# ADS1299.net
KiCad netlist of a schematic drawn in Altium Designer
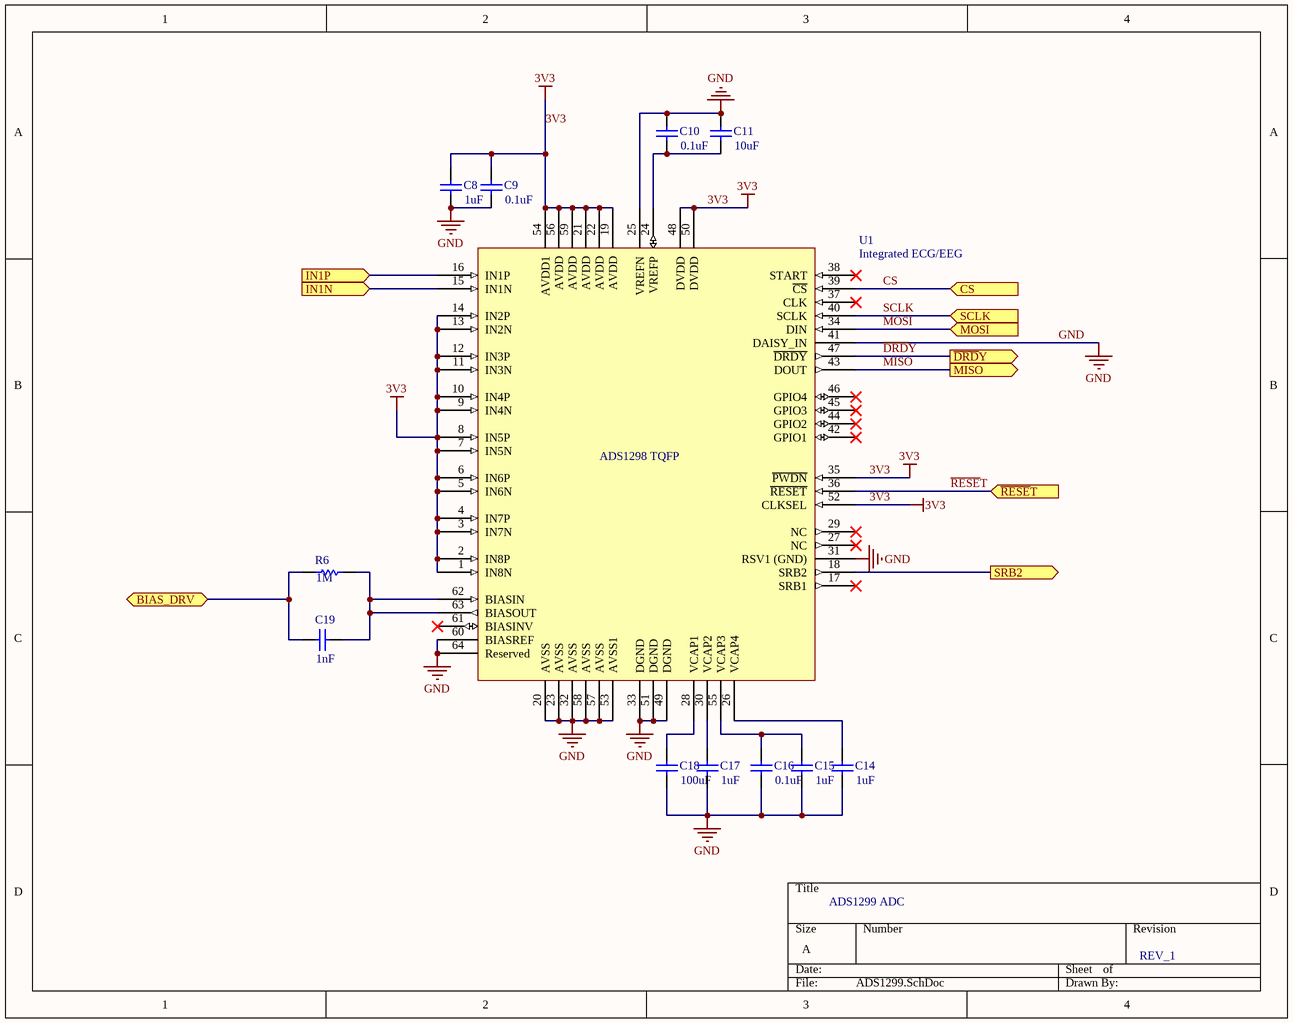
[diagram p0: ADS1299.SchDoc]

(export (version "E")
  (design (tool "Eeschema 10.0.6"))
  (components
    (comp (ref "C8")
      (value "1uF")
      (footprint "1608[0603]")
      (description "Capacitor")
      (fields (field (name "Comment") "Cap") (field (name "PUBLISHER") "Altium Limited"))
      (libsource (lib "Miscellaneous Devices") (part "Cap"))
    )
    (comp (ref "C9")
      (value "0.1uF")
      (footprint "1608[0603]")
      (description "Capacitor")
      (fields (field (name "Comment") "Cap") (field (name "PUBLISHER") "Altium Limited"))
      (libsource (lib "Miscellaneous Devices") (part "Cap"))
    )
    (comp (ref "C10")
      (value "0.1uF")
      (footprint "1608[0603]")
      (description "Capacitor")
      (fields (field (name "Comment") "Cap") (field (name "PUBLISHER") "Altium Limited"))
      (libsource (lib "Miscellaneous Devices") (part "Cap"))
    )
    (comp (ref "C11")
      (value "10uF")
      (footprint "1608[0603]")
      (description "Capacitor")
      (fields (field (name "Comment") "Cap") (field (name "PUBLISHER") "Altium Limited"))
      (libsource (lib "Miscellaneous Devices") (part "Cap"))
    )
    (comp (ref "C14")
      (value "1uF")
      (footprint "1608[0603]")
      (description "Capacitor")
      (fields (field (name "Comment") "Cap") (field (name "PUBLISHER") "Altium Limited"))
      (libsource (lib "Miscellaneous Devices") (part "Cap"))
    )
    (comp (ref "C15")
      (value "1uF")
      (footprint "1608[0603]")
      (description "Capacitor")
      (fields (field (name "Comment") "Cap") (field (name "PUBLISHER") "Altium Limited"))
      (libsource (lib "Miscellaneous Devices") (part "Cap"))
    )
    (comp (ref "C16")
      (value "0.1uF")
      (footprint "1608[0603]")
      (description "Capacitor")
      (fields (field (name "Comment") "Cap") (field (name "PUBLISHER") "Altium Limited"))
      (libsource (lib "Miscellaneous Devices") (part "Cap"))
    )
    (comp (ref "C17")
      (value "1uF")
      (footprint "1608[0603]")
      (description "Capacitor")
      (fields (field (name "Comment") "Cap") (field (name "PUBLISHER") "Altium Limited"))
      (libsource (lib "Miscellaneous Devices") (part "Cap"))
    )
    (comp (ref "C18")
      (value "100uF")
      (footprint "1608[0603]")
      (description "Capacitor")
      (fields (field (name "Comment") "Cap") (field (name "PUBLISHER") "Altium Limited"))
      (libsource (lib "Miscellaneous Devices") (part "Cap"))
    )
    (comp (ref "C19")
      (value "1nF")
      (footprint "1608[0603]")
      (description "Capacitor")
      (fields (field (name "Comment") "Cap") (field (name "PUBLISHER") "Altium Limited"))
      (libsource (lib "Miscellaneous Devices") (part "Cap"))
    )
    (comp (ref "R6")
      (value "1M")
      (footprint "1608[0603]")
      (description "Resistor")
      (fields (field (name "Comment") "Res") (field (name "PUBLISHER") "Altium Limited"))
      (libsource (lib "Miscellaneous Devices") (part "Res1"))
    )
    (comp (ref "U1")
      (value "Integrated ECG/EEG")
      (footprint "ADS1298:TQFP-PT64_N")
      (libsource (lib "ads1298") (part "ADS1298-TQFP"))
    )
  )
  (nets
    (net (code "1") (name "/BIAS_DRV") (class "Default")
      (node (ref "C19") (pin "2") (pinfunction "2_2") (pintype "passive"))
      (node (ref "R6") (pin "2") (pinfunction "2_2") (pintype "passive"))
    )
    (net (code "2") (name "/CS") (class "Default")
      (node (ref "U1") (pin "39") (pinfunction "~{CS}_39") (pintype "input"))
    )
    (net (code "3") (name "/IN1N") (class "Default")
      (node (ref "U1") (pin "15") (pinfunction "IN1N_15") (pintype "input"))
    )
    (net (code "4") (name "/IN1P") (class "Default")
      (node (ref "U1") (pin "16") (pinfunction "IN1P_16") (pintype "input"))
    )
    (net (code "5") (name "/MISO") (class "Default")
      (node (ref "U1") (pin "43") (pinfunction "DOUT_43") (pintype "output"))
    )
    (net (code "6") (name "/MOSI") (class "Default")
      (node (ref "U1") (pin "34") (pinfunction "DIN_34") (pintype "input"))
    )
    (net (code "7") (name "/SCLK") (class "Default")
      (node (ref "U1") (pin "40") (pinfunction "SCLK_40") (pintype "input"))
    )
    (net (code "8") (name "/SRB2") (class "Default")
      (node (ref "U1") (pin "18") (pinfunction "SRB2_18") (pintype "output"))
    )
    (net (code "9") (name "/~{DRD}Y") (class "Default")
      (node (ref "U1") (pin "47") (pinfunction "~{DRDY}_47") (pintype "output"))
    )
    (net (code "10") (name "/~{RESE}T") (class "Default")
      (node (ref "U1") (pin "36") (pinfunction "~{RESET}_36") (pintype "input"))
    )
    (net (code "11") (name "3V3") (class "Default")
      (node (ref "C8") (pin "2") (pinfunction "2_2") (pintype "passive"))
      (node (ref "C9") (pin "2") (pinfunction "2_2") (pintype "passive"))
      (node (ref "U1") (pin "1") (pinfunction "IN8N_1") (pintype "input"))
      (node (ref "U1") (pin "10") (pinfunction "IN4P_10") (pintype "input"))
      (node (ref "U1") (pin "11") (pinfunction "IN3N_11") (pintype "input"))
      (node (ref "U1") (pin "12") (pinfunction "IN3P_12") (pintype "input"))
      (node (ref "U1") (pin "13") (pinfunction "IN2N_13") (pintype "input"))
      (node (ref "U1") (pin "14") (pinfunction "IN2P_14") (pintype "input"))
      (node (ref "U1") (pin "19") (pinfunction "AVDD_19") (pintype "power_in"))
      (node (ref "U1") (pin "2") (pinfunction "IN8P_2") (pintype "input"))
      (node (ref "U1") (pin "21") (pinfunction "AVDD_21") (pintype "power_in"))
      (node (ref "U1") (pin "22") (pinfunction "AVDD_22") (pintype "power_in"))
      (node (ref "U1") (pin "3") (pinfunction "IN7N_3") (pintype "input"))
      (node (ref "U1") (pin "35") (pinfunction "~{PWDN}_35") (pintype "input"))
      (node (ref "U1") (pin "4") (pinfunction "IN7P_4") (pintype "input"))
      (node (ref "U1") (pin "48") (pinfunction "DVDD_48") (pintype "power_in"))
      (node (ref "U1") (pin "5") (pinfunction "IN6N_5") (pintype "input"))
      (node (ref "U1") (pin "50") (pinfunction "DVDD_50") (pintype "power_in"))
      (node (ref "U1") (pin "52") (pinfunction "CLKSEL_52") (pintype "input"))
      (node (ref "U1") (pin "54") (pinfunction "AVDD1_54") (pintype "power_in"))
      (node (ref "U1") (pin "56") (pinfunction "AVDD_56") (pintype "power_in"))
      (node (ref "U1") (pin "59") (pinfunction "AVDD_59") (pintype "power_in"))
      (node (ref "U1") (pin "6") (pinfunction "IN6P_6") (pintype "input"))
      (node (ref "U1") (pin "7") (pinfunction "IN5N_7") (pintype "input"))
      (node (ref "U1") (pin "8") (pinfunction "IN5P_8") (pintype "input"))
      (node (ref "U1") (pin "9") (pinfunction "IN4N_9") (pintype "input"))
    )
    (net (code "12") (name "GND") (class "Default")
      (node (ref "C10") (pin "2") (pinfunction "2_2") (pintype "passive"))
      (node (ref "C11") (pin "2") (pinfunction "2_2") (pintype "passive"))
      (node (ref "C14") (pin "1") (pinfunction "1_1") (pintype "passive"))
      (node (ref "C15") (pin "1") (pinfunction "1_1") (pintype "passive"))
      (node (ref "C16") (pin "1") (pinfunction "1_1") (pintype "passive"))
      (node (ref "C17") (pin "1") (pinfunction "1_1") (pintype "passive"))
      (node (ref "C18") (pin "1") (pinfunction "1_1") (pintype "passive"))
      (node (ref "C8") (pin "1") (pinfunction "1_1") (pintype "passive"))
      (node (ref "C9") (pin "1") (pinfunction "1_1") (pintype "passive"))
      (node (ref "U1") (pin "20") (pinfunction "AVSS_20") (pintype "power_in"))
      (node (ref "U1") (pin "23") (pinfunction "AVSS_23") (pintype "power_in"))
      (node (ref "U1") (pin "25") (pinfunction "VREFN_25") (pintype "power_in"))
      (node (ref "U1") (pin "31") (pinfunction "RSV1_(GND)_31") (pintype "power_in"))
      (node (ref "U1") (pin "32") (pinfunction "AVSS_32") (pintype "power_in"))
      (node (ref "U1") (pin "33") (pinfunction "DGND_33") (pintype "power_in"))
      (node (ref "U1") (pin "41") (pinfunction "DAISY_IN_41") (pintype "power_in"))
      (node (ref "U1") (pin "49") (pinfunction "DGND_49") (pintype "power_in"))
      (node (ref "U1") (pin "51") (pinfunction "DGND_51") (pintype "passive"))
      (node (ref "U1") (pin "53") (pinfunction "AVSS1_53") (pintype "power_in"))
      (node (ref "U1") (pin "57") (pinfunction "AVSS_57") (pintype "power_in"))
      (node (ref "U1") (pin "58") (pinfunction "AVSS_58") (pintype "power_in"))
      (node (ref "U1") (pin "60") (pinfunction "BIASREF_60") (pintype "power_in"))
      (node (ref "U1") (pin "64") (pinfunction "Reserved_64") (pintype "power_in"))
    )
    (net (code "13") (name "Net-(U1-BIASIN)") (class "Default")
      (node (ref "C19") (pin "1") (pinfunction "1_1") (pintype "passive"))
      (node (ref "R6") (pin "1") (pinfunction "1_1") (pintype "passive"))
      (node (ref "U1") (pin "62") (pinfunction "BIASIN_62") (pintype "input"))
      (node (ref "U1") (pin "63") (pinfunction "BIASOUT_63") (pintype "output"))
    )
    (net (code "14") (name "Net-(U1-VCAP1)") (class "Default")
      (node (ref "C18") (pin "2") (pinfunction "2_2") (pintype "passive"))
      (node (ref "U1") (pin "28") (pinfunction "VCAP1_28") (pintype "power_in"))
    )
    (net (code "15") (name "Net-(U1-VCAP2)") (class "Default")
      (node (ref "C17") (pin "2") (pinfunction "2_2") (pintype "passive"))
      (node (ref "U1") (pin "30") (pinfunction "VCAP2_30") (pintype "passive"))
    )
    (net (code "16") (name "Net-(U1-VCAP3)") (class "Default")
      (node (ref "C15") (pin "2") (pinfunction "2_2") (pintype "passive"))
      (node (ref "C16") (pin "2") (pinfunction "2_2") (pintype "passive"))
      (node (ref "U1") (pin "55") (pinfunction "VCAP3_55") (pintype "passive"))
    )
    (net (code "17") (name "Net-(U1-VCAP4)") (class "Default")
      (node (ref "C14") (pin "2") (pinfunction "2_2") (pintype "passive"))
      (node (ref "U1") (pin "26") (pinfunction "VCAP4_26") (pintype "passive"))
    )
    (net (code "18") (name "Net-(U1-VREFP)") (class "Default")
      (node (ref "C10") (pin "1") (pinfunction "1_1") (pintype "passive"))
      (node (ref "C11") (pin "1") (pinfunction "1_1") (pintype "passive"))
      (node (ref "U1") (pin "24") (pinfunction "VREFP_24") (pintype "bidirectional"))
    )
    (net (code "19") (name "unconnected-(U1-BIASINV-Pad61)") (class "Default")
      (node (ref "U1") (pin "61") (pinfunction "BIASINV_61") (pintype "bidirectional+no_connect"))
    )
    (net (code "20") (name "unconnected-(U1-CLK-Pad37)") (class "Default")
      (node (ref "U1") (pin "37") (pinfunction "CLK_37") (pintype "input+no_connect"))
    )
    (net (code "21") (name "unconnected-(U1-GPIO1-Pad42)") (class "Default")
      (node (ref "U1") (pin "42") (pinfunction "GPIO1_42") (pintype "bidirectional+no_connect"))
    )
    (net (code "22") (name "unconnected-(U1-GPIO2-Pad44)") (class "Default")
      (node (ref "U1") (pin "44") (pinfunction "GPIO2_44") (pintype "bidirectional+no_connect"))
    )
    (net (code "23") (name "unconnected-(U1-GPIO3-Pad45)") (class "Default")
      (node (ref "U1") (pin "45") (pinfunction "GPIO3_45") (pintype "bidirectional+no_connect"))
    )
    (net (code "24") (name "unconnected-(U1-GPIO4-Pad46)") (class "Default")
      (node (ref "U1") (pin "46") (pinfunction "GPIO4_46") (pintype "bidirectional+no_connect"))
    )
    (net (code "25") (name "unconnected-(U1-NC-Pad27)") (class "Default")
      (node (ref "U1") (pin "27") (pinfunction "NC_27") (pintype "output+no_connect"))
    )
    (net (code "26") (name "unconnected-(U1-NC-Pad29)") (class "Default")
      (node (ref "U1") (pin "29") (pinfunction "NC_29") (pintype "output+no_connect"))
    )
    (net (code "27") (name "unconnected-(U1-SRB1-Pad17)") (class "Default")
      (node (ref "U1") (pin "17") (pinfunction "SRB1_17") (pintype "output+no_connect"))
    )
    (net (code "28") (name "unconnected-(U1-START-Pad38)") (class "Default")
      (node (ref "U1") (pin "38") (pinfunction "START_38") (pintype "input+no_connect"))
    )
  )
)
